# 04-PCIe_JTAG.net
KiCad netlist of a schematic drawn in Altium Designer
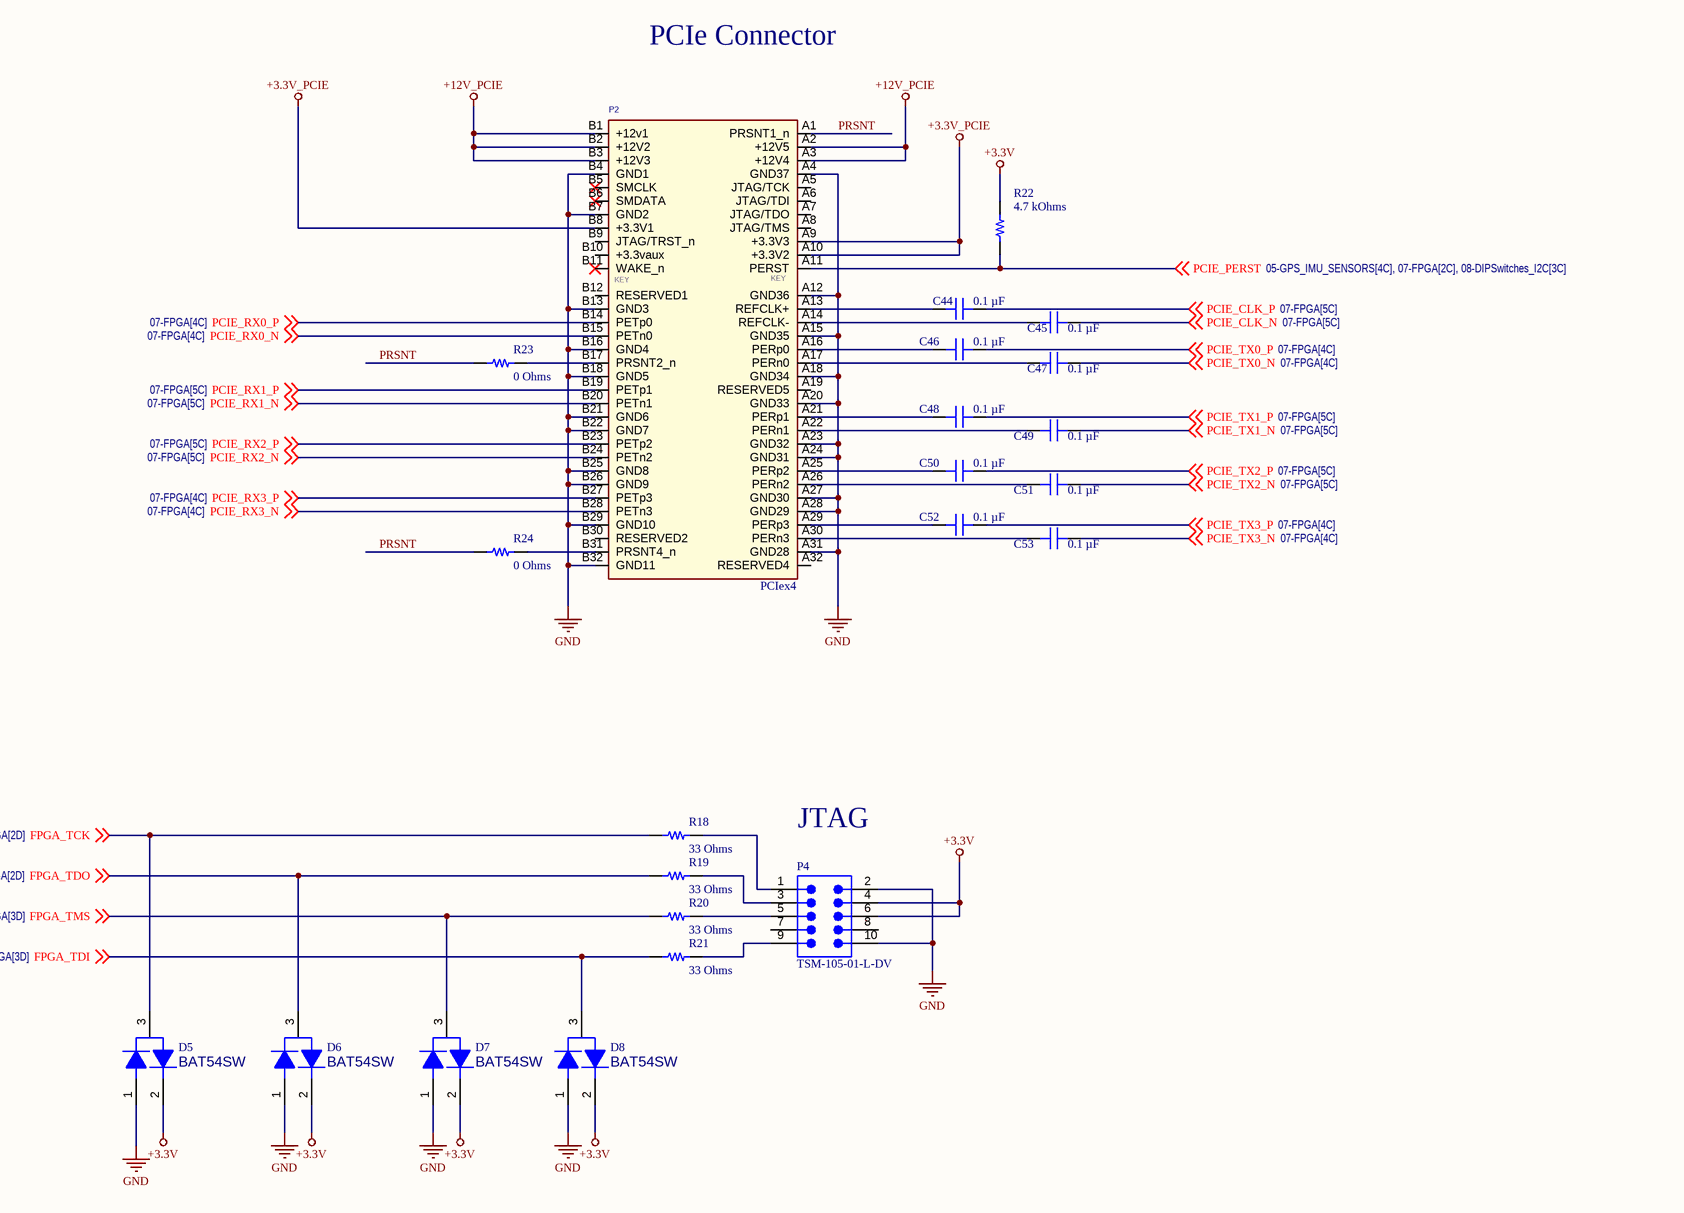
[diagram p0: 04-PCIe_JTAG.SchDoc]

(export (version "E")
  (design (tool "Eeschema 10.0.6"))
  (components
    (comp (ref "C44")
      (value "0.1 µF")
      (footprint "CAP 0402_1005")
      (description "CAP CER 0.1UF 50V X7R 0402")
      (fields (field (name "PART NUMBER") "CC0402KRX7R9BB104") (field (name "MANUFACTURER") "Yageo"))
      (libsource (lib "Celestial Altium Library - altium_library") (part "Capacitor"))
    )
    (comp (ref "C45")
      (value "0.1 µF")
      (footprint "CAP 0402_1005")
      (description "CAP CER 0.1UF 50V X7R 0402")
      (fields (field (name "PART NUMBER") "CC0402KRX7R9BB104") (field (name "MANUFACTURER") "Yageo"))
      (libsource (lib "Celestial Altium Library - altium_library") (part "Capacitor"))
    )
    (comp (ref "C46")
      (value "0.1 µF")
      (footprint "CAP 0402_1005")
      (description "CAP CER 0.1UF 50V X7R 0402")
      (fields (field (name "PART NUMBER") "CC0402KRX7R9BB104") (field (name "MANUFACTURER") "Yageo"))
      (libsource (lib "Celestial Altium Library - altium_library") (part "Capacitor"))
    )
    (comp (ref "C47")
      (value "0.1 µF")
      (footprint "CAP 0402_1005")
      (description "CAP CER 0.1UF 50V X7R 0402")
      (fields (field (name "PART NUMBER") "CC0402KRX7R9BB104") (field (name "MANUFACTURER") "Yageo"))
      (libsource (lib "Celestial Altium Library - altium_library") (part "Capacitor"))
    )
    (comp (ref "C48")
      (value "0.1 µF")
      (footprint "CAP 0402_1005")
      (description "CAP CER 0.1UF 50V X7R 0402")
      (fields (field (name "PART NUMBER") "CC0402KRX7R9BB104") (field (name "MANUFACTURER") "Yageo"))
      (libsource (lib "Celestial Altium Library - altium_library") (part "Capacitor"))
    )
    (comp (ref "C49")
      (value "0.1 µF")
      (footprint "CAP 0402_1005")
      (description "CAP CER 0.1UF 50V X7R 0402")
      (fields (field (name "PART NUMBER") "CC0402KRX7R9BB104") (field (name "MANUFACTURER") "Yageo"))
      (libsource (lib "Celestial Altium Library - altium_library") (part "Capacitor"))
    )
    (comp (ref "C50")
      (value "0.1 µF")
      (footprint "CAP 0402_1005")
      (description "CAP CER 0.1UF 50V X7R 0402")
      (fields (field (name "PART NUMBER") "CC0402KRX7R9BB104") (field (name "MANUFACTURER") "Yageo"))
      (libsource (lib "Celestial Altium Library - altium_library") (part "Capacitor"))
    )
    (comp (ref "C51")
      (value "0.1 µF")
      (footprint "CAP 0402_1005")
      (description "CAP CER 0.1UF 50V X7R 0402")
      (fields (field (name "PART NUMBER") "CC0402KRX7R9BB104") (field (name "MANUFACTURER") "Yageo"))
      (libsource (lib "Celestial Altium Library - altium_library") (part "Capacitor"))
    )
    (comp (ref "C52")
      (value "0.1 µF")
      (footprint "CAP 0402_1005")
      (description "CAP CER 0.1UF 50V X7R 0402")
      (fields (field (name "PART NUMBER") "CC0402KRX7R9BB104") (field (name "MANUFACTURER") "Yageo"))
      (libsource (lib "Celestial Altium Library - altium_library") (part "Capacitor"))
    )
    (comp (ref "C53")
      (value "0.1 µF")
      (footprint "CAP 0402_1005")
      (description "CAP CER 0.1UF 50V X7R 0402")
      (fields (field (name "PART NUMBER") "CC0402KRX7R9BB104") (field (name "MANUFACTURER") "Yageo"))
      (libsource (lib "Celestial Altium Library - altium_library") (part "Capacitor"))
    )
    (comp (ref "D5")
      (value "BAT54SW")
      (footprint "SOT65P210X110-3N")
      (description "DIO, SCHOTTKY, BAT54S, DUAL SERIES, 30V, 200MA, SC-70")
      (fields (field (name "MFG PART NUM") "BAT54SWQ-7-F") (field (name "VALENTIUM PART NUM") "<VALENTIUM>"))
      (libsource (lib "Passives") (part "BAT54SW"))
    )
    (comp (ref "D6")
      (value "BAT54SW")
      (footprint "SOT65P210X110-3N")
      (description "DIO, SCHOTTKY, BAT54S, DUAL SERIES, 30V, 200MA, SC-70")
      (fields (field (name "MFG PART NUM") "BAT54SWQ-7-F") (field (name "VALENTIUM PART NUM") "<VALENTIUM>"))
      (libsource (lib "Passives") (part "BAT54SW"))
    )
    (comp (ref "D7")
      (value "BAT54SW")
      (footprint "SOT65P210X110-3N")
      (description "DIO, SCHOTTKY, BAT54S, DUAL SERIES, 30V, 200MA, SC-70")
      (fields (field (name "MFG PART NUM") "BAT54SWQ-7-F") (field (name "VALENTIUM PART NUM") "<VALENTIUM>"))
      (libsource (lib "Passives") (part "BAT54SW"))
    )
    (comp (ref "D8")
      (value "BAT54SW")
      (footprint "SOT65P210X110-3N")
      (description "DIO, SCHOTTKY, BAT54S, DUAL SERIES, 30V, 200MA, SC-70")
      (fields (field (name "MFG PART NUM") "BAT54SWQ-7-F") (field (name "VALENTIUM PART NUM") "<VALENTIUM>"))
      (libsource (lib "Passives") (part "BAT54SW"))
    )
    (comp (ref "P2")
      (value "PCIex4")
      (footprint "PCIE_4LANE_EDGE")
      (description "PCIE x4 Edge Connector,OrCAD Symbol,NC")
      (fields (field (name "PART NUMBER") "451") (field (name "MANUFACTURER") "NA"))
      (libsource (lib "Connectors") (part "PCIex4"))
    )
    (comp (ref "P4")
      (value "TSM-105-01-L-DV")
      (footprint "SMTC-TSM-105-01-X-DV")
      (fields (field (name "MANUFACTURER") "Samtec"))
      (libsource (lib "Altium Content Vault") (part "SMTC-TSM-105-01-X-X"))
    )
    (comp (ref "R18")
      (value "33 Ohms")
      (footprint "YAGEO RES 0805_2012")
      (description "RES 33 OHM 1% 1/8W 0805")
      (fields (field (name "PART NUMBER") "RC0805FR-0733RL") (field (name "MANUFACTURER") "Yageo"))
      (libsource (lib "Celestial Altium Library - altium_library") (part "Resistor"))
    )
    (comp (ref "R19")
      (value "33 Ohms")
      (footprint "YAGEO RES 0805_2012")
      (description "RES 33 OHM 1% 1/8W 0805")
      (fields (field (name "PART NUMBER") "RC0805FR-0733RL") (field (name "MANUFACTURER") "Yageo"))
      (libsource (lib "Celestial Altium Library - altium_library") (part "Resistor"))
    )
    (comp (ref "R20")
      (value "33 Ohms")
      (footprint "YAGEO RES 0805_2012")
      (description "RES 33 OHM 1% 1/8W 0805")
      (fields (field (name "PART NUMBER") "RC0805FR-0733RL") (field (name "MANUFACTURER") "Yageo"))
      (libsource (lib "Celestial Altium Library - altium_library") (part "Resistor"))
    )
    (comp (ref "R21")
      (value "33 Ohms")
      (footprint "YAGEO RES 0805_2012")
      (description "RES 33 OHM 1% 1/8W 0805")
      (fields (field (name "PART NUMBER") "RC0805FR-0733RL") (field (name "MANUFACTURER") "Yageo"))
      (libsource (lib "Celestial Altium Library - altium_library") (part "Resistor"))
    )
    (comp (ref "R22")
      (value "4.7 kOhms")
      (footprint "YAGEO RES 0402_1005")
      (description "RES 4.7K OHM 1% 1/16W 0402")
      (fields (field (name "PART NUMBER") "RC0402FR-074K7L") (field (name "MANUFACTURER") "Yageo"))
      (libsource (lib "Celestial Altium Library - altium_library") (part "Resistor"))
    )
    (comp (ref "R23")
      (value "0 Ohms")
      (footprint "YAGEO RES 0402_1005")
      (description "RES 0 OHM JUMPER 1/16W 0402")
      (fields (field (name "PART NUMBER") "RC0402FR-070RL") (field (name "MANUFACTURER") "Yageo"))
      (libsource (lib "Celestial Altium Library - altium_library") (part "Resistor"))
    )
    (comp (ref "R24")
      (value "0 Ohms")
      (footprint "YAGEO RES 0402_1005")
      (description "RES 0 OHM JUMPER 1/16W 0402")
      (fields (field (name "PART NUMBER") "RC0402FR-070RL") (field (name "MANUFACTURER") "Yageo"))
      (libsource (lib "Celestial Altium Library - altium_library") (part "Resistor"))
    )
  )
  (nets
    (net (code "1") (name "+3.3V") (class "Default")
      (node (ref "D5") (pin "2") (pinfunction "2_2") (pintype "passive"))
      (node (ref "D6") (pin "2") (pinfunction "2_2") (pintype "passive"))
      (node (ref "D7") (pin "2") (pinfunction "2_2") (pintype "passive"))
      (node (ref "D8") (pin "2") (pinfunction "2_2") (pintype "passive"))
      (node (ref "P4") (pin "4") (pinfunction "4_4") (pintype "passive"))
      (node (ref "P4") (pin "6") (pinfunction "6_6") (pintype "passive"))
      (node (ref "R22") (pin "2") (pinfunction "2_2") (pintype "passive"))
    )
    (net (code "2") (name "+3.3V_PCIE") (class "Default")
      (node (ref "P2") (pin "A10") (pinfunction "+3.3V2_A10") (pintype "passive"))
      (node (ref "P2") (pin "A9") (pinfunction "+3.3V3_A9") (pintype "passive"))
      (node (ref "P2") (pin "B8") (pinfunction "+3.3V1_B8") (pintype "power_in"))
    )
    (net (code "3") (name "+12V_PCIE") (class "Default")
      (node (ref "P2") (pin "A2") (pinfunction "+12V5_A2") (pintype "passive"))
      (node (ref "P2") (pin "A3") (pinfunction "+12V4_A3") (pintype "passive"))
      (node (ref "P2") (pin "B1") (pinfunction "+12v1_B1") (pintype "power_in"))
      (node (ref "P2") (pin "B2") (pinfunction "+12V2_B2") (pintype "power_in"))
      (node (ref "P2") (pin "B3") (pinfunction "+12V3_B3") (pintype "power_in"))
    )
    (net (code "4") (name "/PRSNT") (class "Default")
      (node (ref "P2") (pin "A1") (pinfunction "PRSNT1_n_A1") (pintype "passive"))
      (node (ref "R23") (pin "1") (pinfunction "1_1") (pintype "passive"))
      (node (ref "R24") (pin "1") (pinfunction "1_1") (pintype "passive"))
    )
    (net (code "5") (name "FPGA_TCK") (class "Default")
      (node (ref "D5") (pin "3") (pinfunction "3_3") (pintype "passive"))
      (node (ref "R18") (pin "1") (pinfunction "1_1") (pintype "passive"))
    )
    (net (code "6") (name "FPGA_TDI") (class "Default")
      (node (ref "D8") (pin "3") (pinfunction "3_3") (pintype "passive"))
      (node (ref "R21") (pin "1") (pinfunction "1_1") (pintype "passive"))
    )
    (net (code "7") (name "FPGA_TDO") (class "Default")
      (node (ref "D6") (pin "3") (pinfunction "3_3") (pintype "passive"))
      (node (ref "R19") (pin "1") (pinfunction "1_1") (pintype "passive"))
    )
    (net (code "8") (name "FPGA_TMS") (class "Default")
      (node (ref "D7") (pin "3") (pinfunction "3_3") (pintype "passive"))
      (node (ref "R20") (pin "1") (pinfunction "1_1") (pintype "passive"))
    )
    (net (code "9") (name "GND") (class "Default")
      (node (ref "D5") (pin "1") (pinfunction "1_1") (pintype "passive"))
      (node (ref "D6") (pin "1") (pinfunction "1_1") (pintype "passive"))
      (node (ref "D7") (pin "1") (pinfunction "1_1") (pintype "passive"))
      (node (ref "D8") (pin "1") (pinfunction "1_1") (pintype "passive"))
      (node (ref "P2") (pin "A12") (pinfunction "GND36_A12") (pintype "power_in"))
      (node (ref "P2") (pin "A15") (pinfunction "GND35_A15") (pintype "power_in"))
      (node (ref "P2") (pin "A18") (pinfunction "GND34_A18") (pintype "power_in"))
      (node (ref "P2") (pin "A20") (pinfunction "GND33_A20") (pintype "power_in"))
      (node (ref "P2") (pin "A23") (pinfunction "GND32_A23") (pintype "power_in"))
      (node (ref "P2") (pin "A24") (pinfunction "GND31_A24") (pintype "power_in"))
      (node (ref "P2") (pin "A27") (pinfunction "GND30_A27") (pintype "power_in"))
      (node (ref "P2") (pin "A28") (pinfunction "GND29_A28") (pintype "power_in"))
      (node (ref "P2") (pin "A31") (pinfunction "GND28_A31") (pintype "power_in"))
      (node (ref "P2") (pin "A4") (pinfunction "GND37_A4") (pintype "power_in"))
      (node (ref "P2") (pin "B13") (pinfunction "GND3_B13") (pintype "power_in"))
      (node (ref "P2") (pin "B16") (pinfunction "GND4_B16") (pintype "power_in"))
      (node (ref "P2") (pin "B18") (pinfunction "GND5_B18") (pintype "power_in"))
      (node (ref "P2") (pin "B21") (pinfunction "GND6_B21") (pintype "power_in"))
      (node (ref "P2") (pin "B22") (pinfunction "GND7_B22") (pintype "power_in"))
      (node (ref "P2") (pin "B25") (pinfunction "GND8_B25") (pintype "power_in"))
      (node (ref "P2") (pin "B26") (pinfunction "GND9_B26") (pintype "power_in"))
      (node (ref "P2") (pin "B29") (pinfunction "GND10_B29") (pintype "power_in"))
      (node (ref "P2") (pin "B32") (pinfunction "GND11_B32") (pintype "power_in"))
      (node (ref "P2") (pin "B4") (pinfunction "GND1_B4") (pintype "power_in"))
      (node (ref "P2") (pin "B7") (pinfunction "GND2_B7") (pintype "power_in"))
      (node (ref "P4") (pin "10") (pinfunction "10_10") (pintype "passive"))
      (node (ref "P4") (pin "2") (pinfunction "2_2") (pintype "passive"))
    )
    (net (code "10") (name "Net-(P2-PERn0)") (class "Default")
      (node (ref "C47") (pin "1") (pinfunction "1_1") (pintype "passive"))
      (node (ref "P2") (pin "A17") (pinfunction "PERn0_A17") (pintype "passive"))
    )
    (net (code "11") (name "Net-(P2-PERn1)") (class "Default")
      (node (ref "C49") (pin "1") (pinfunction "1_1") (pintype "passive"))
      (node (ref "P2") (pin "A22") (pinfunction "PERn1_A22") (pintype "passive"))
    )
    (net (code "12") (name "Net-(P2-PERn2)") (class "Default")
      (node (ref "C51") (pin "1") (pinfunction "1_1") (pintype "passive"))
      (node (ref "P2") (pin "A26") (pinfunction "PERn2_A26") (pintype "passive"))
    )
    (net (code "13") (name "Net-(P2-PERn3)") (class "Default")
      (node (ref "C53") (pin "1") (pinfunction "1_1") (pintype "passive"))
      (node (ref "P2") (pin "A30") (pinfunction "PERn3_A30") (pintype "passive"))
    )
    (net (code "14") (name "Net-(P2-PERp0)") (class "Default")
      (node (ref "C46") (pin "1") (pinfunction "1_1") (pintype "passive"))
      (node (ref "P2") (pin "A16") (pinfunction "PERp0_A16") (pintype "passive"))
    )
    (net (code "15") (name "Net-(P2-PERp1)") (class "Default")
      (node (ref "C48") (pin "1") (pinfunction "1_1") (pintype "passive"))
      (node (ref "P2") (pin "A21") (pinfunction "PERp1_A21") (pintype "passive"))
    )
    (net (code "16") (name "Net-(P2-PERp2)") (class "Default")
      (node (ref "C50") (pin "1") (pinfunction "1_1") (pintype "passive"))
      (node (ref "P2") (pin "A25") (pinfunction "PERp2_A25") (pintype "passive"))
    )
    (net (code "17") (name "Net-(P2-PERp3)") (class "Default")
      (node (ref "C52") (pin "1") (pinfunction "1_1") (pintype "passive"))
      (node (ref "P2") (pin "A29") (pinfunction "PERp3_A29") (pintype "passive"))
    )
    (net (code "18") (name "Net-(P2-PRSNT2_n)") (class "Default")
      (node (ref "P2") (pin "B17") (pinfunction "PRSNT2_n_B17") (pintype "passive"))
      (node (ref "R23") (pin "2") (pinfunction "2_2") (pintype "passive"))
    )
    (net (code "19") (name "Net-(P2-PRSNT4_n)") (class "Default")
      (node (ref "P2") (pin "B31") (pinfunction "PRSNT4_n_B31") (pintype "passive"))
      (node (ref "R24") (pin "2") (pinfunction "2_2") (pintype "passive"))
    )
    (net (code "20") (name "Net-(P2-REFCLK+)") (class "Default")
      (node (ref "C44") (pin "1") (pinfunction "1_1") (pintype "passive"))
      (node (ref "P2") (pin "A13") (pinfunction "REFCLK+_A13") (pintype "passive"))
    )
    (net (code "21") (name "Net-(P2-REFCLK-)") (class "Default")
      (node (ref "C45") (pin "1") (pinfunction "1_1") (pintype "passive"))
      (node (ref "P2") (pin "A14") (pinfunction "REFCLK-_A14") (pintype "passive"))
    )
    (net (code "22") (name "Net-(P4-Pad1)") (class "Default")
      (node (ref "P4") (pin "1") (pinfunction "1_1") (pintype "passive"))
      (node (ref "R18") (pin "2") (pinfunction "2_2") (pintype "passive"))
    )
    (net (code "23") (name "Net-(P4-Pad3)") (class "Default")
      (node (ref "P4") (pin "3") (pinfunction "3_3") (pintype "passive"))
      (node (ref "R19") (pin "2") (pinfunction "2_2") (pintype "passive"))
    )
    (net (code "24") (name "Net-(P4-Pad5)") (class "Default")
      (node (ref "P4") (pin "5") (pinfunction "5_5") (pintype "passive"))
      (node (ref "R20") (pin "2") (pinfunction "2_2") (pintype "passive"))
    )
    (net (code "25") (name "Net-(P4-Pad9)") (class "Default")
      (node (ref "P4") (pin "9") (pinfunction "9_9") (pintype "passive"))
      (node (ref "R21") (pin "2") (pinfunction "2_2") (pintype "passive"))
    )
    (net (code "26") (name "PCIE_CLK_N") (class "Default")
      (node (ref "C45") (pin "2") (pinfunction "2_2") (pintype "passive"))
    )
    (net (code "27") (name "PCIE_CLK_P") (class "Default")
      (node (ref "C44") (pin "2") (pinfunction "2_2") (pintype "passive"))
    )
    (net (code "28") (name "PCIE_PERST") (class "Default")
      (node (ref "P2") (pin "A11") (pinfunction "PERST_A11") (pintype "passive"))
      (node (ref "R22") (pin "1") (pinfunction "1_1") (pintype "passive"))
    )
    (net (code "29") (name "PCIE_RX0_N") (class "Default")
      (node (ref "P2") (pin "B15") (pinfunction "PETn0_B15") (pintype "passive"))
    )
    (net (code "30") (name "PCIE_RX0_P") (class "Default")
      (node (ref "P2") (pin "B14") (pinfunction "PETp0_B14") (pintype "passive"))
    )
    (net (code "31") (name "PCIE_RX1_N") (class "Default")
      (node (ref "P2") (pin "B20") (pinfunction "PETn1_B20") (pintype "passive"))
    )
    (net (code "32") (name "PCIE_RX1_P") (class "Default")
      (node (ref "P2") (pin "B19") (pinfunction "PETp1_B19") (pintype "passive"))
    )
    (net (code "33") (name "PCIE_RX2_N") (class "Default")
      (node (ref "P2") (pin "B24") (pinfunction "PETn2_B24") (pintype "passive"))
    )
    (net (code "34") (name "PCIE_RX2_P") (class "Default")
      (node (ref "P2") (pin "B23") (pinfunction "PETp2_B23") (pintype "passive"))
    )
    (net (code "35") (name "PCIE_RX3_N") (class "Default")
      (node (ref "P2") (pin "B28") (pinfunction "PETn3_B28") (pintype "passive"))
    )
    (net (code "36") (name "PCIE_RX3_P") (class "Default")
      (node (ref "P2") (pin "B27") (pinfunction "PETp3_B27") (pintype "passive"))
    )
    (net (code "37") (name "PCIE_TX0_N") (class "Default")
      (node (ref "C47") (pin "2") (pinfunction "2_2") (pintype "passive"))
    )
    (net (code "38") (name "PCIE_TX0_P") (class "Default")
      (node (ref "C46") (pin "2") (pinfunction "2_2") (pintype "passive"))
    )
    (net (code "39") (name "PCIE_TX1_N") (class "Default")
      (node (ref "C49") (pin "2") (pinfunction "2_2") (pintype "passive"))
    )
    (net (code "40") (name "PCIE_TX1_P") (class "Default")
      (node (ref "C48") (pin "2") (pinfunction "2_2") (pintype "passive"))
    )
    (net (code "41") (name "PCIE_TX2_N") (class "Default")
      (node (ref "C51") (pin "2") (pinfunction "2_2") (pintype "passive"))
    )
    (net (code "42") (name "PCIE_TX2_P") (class "Default")
      (node (ref "C50") (pin "2") (pinfunction "2_2") (pintype "passive"))
    )
    (net (code "43") (name "PCIE_TX3_N") (class "Default")
      (node (ref "C53") (pin "2") (pinfunction "2_2") (pintype "passive"))
    )
    (net (code "44") (name "PCIE_TX3_P") (class "Default")
      (node (ref "C52") (pin "2") (pinfunction "2_2") (pintype "passive"))
    )
    (net (code "45") (name "unconnected-(P2-+3.3vaux-PadB10)") (class "Default")
      (node (ref "P2") (pin "B10") (pinfunction "+3.3vaux_B10") (pintype "passive"))
    )
    (net (code "46") (name "unconnected-(P2-JTAG{slash}TCK-PadA5)") (class "Default")
      (node (ref "P2") (pin "A5") (pinfunction "JTAG/TCK_A5") (pintype "passive"))
    )
    (net (code "47") (name "unconnected-(P2-JTAG{slash}TDI-PadA6)") (class "Default")
      (node (ref "P2") (pin "A6") (pinfunction "JTAG/TDI_A6") (pintype "passive"))
    )
    (net (code "48") (name "unconnected-(P2-JTAG{slash}TDO-PadA7)") (class "Default")
      (node (ref "P2") (pin "A7") (pinfunction "JTAG/TDO_A7") (pintype "passive"))
    )
    (net (code "49") (name "unconnected-(P2-JTAG{slash}TMS-PadA8)") (class "Default")
      (node (ref "P2") (pin "A8") (pinfunction "JTAG/TMS_A8") (pintype "passive"))
    )
    (net (code "50") (name "unconnected-(P2-JTAG{slash}TRST_n-PadB9)") (class "Default")
      (node (ref "P2") (pin "B9") (pinfunction "JTAG/TRST_n_B9") (pintype "passive"))
    )
    (net (code "51") (name "unconnected-(P2-RESERVED1-PadB12)") (class "Default")
      (node (ref "P2") (pin "B12") (pinfunction "RESERVED1_B12") (pintype "passive"))
    )
    (net (code "52") (name "unconnected-(P2-RESERVED2-PadB30)") (class "Default")
      (node (ref "P2") (pin "B30") (pinfunction "RESERVED2_B30") (pintype "passive"))
    )
    (net (code "53") (name "unconnected-(P2-RESERVED4-PadA32)") (class "Default")
      (node (ref "P2") (pin "A32") (pinfunction "RESERVED4_A32") (pintype "passive"))
    )
    (net (code "54") (name "unconnected-(P2-RESERVED5-PadA19)") (class "Default")
      (node (ref "P2") (pin "A19") (pinfunction "RESERVED5_A19") (pintype "passive"))
    )
    (net (code "55") (name "unconnected-(P2-SMCLK-PadB5)") (class "Default")
      (node (ref "P2") (pin "B5") (pinfunction "SMCLK_B5") (pintype "passive+no_connect"))
    )
    (net (code "56") (name "unconnected-(P2-SMDATA-PadB6)") (class "Default")
      (node (ref "P2") (pin "B6") (pinfunction "SMDATA_B6") (pintype "passive+no_connect"))
    )
    (net (code "57") (name "unconnected-(P2-WAKE_n-PadB11)") (class "Default")
      (node (ref "P2") (pin "B11") (pinfunction "WAKE_n_B11") (pintype "passive+no_connect"))
    )
    (net (code "58") (name "unconnected-(P4-Pad7)") (class "Default")
      (node (ref "P4") (pin "7") (pinfunction "7_7") (pintype "passive"))
    )
    (net (code "59") (name "unconnected-(P4-Pad8)") (class "Default")
      (node (ref "P4") (pin "8") (pinfunction "8_8") (pintype "passive"))
    )
  )
)
